# rcserial60b50ttl.net
KiCad netlist of a schematic drawn in EAGLE
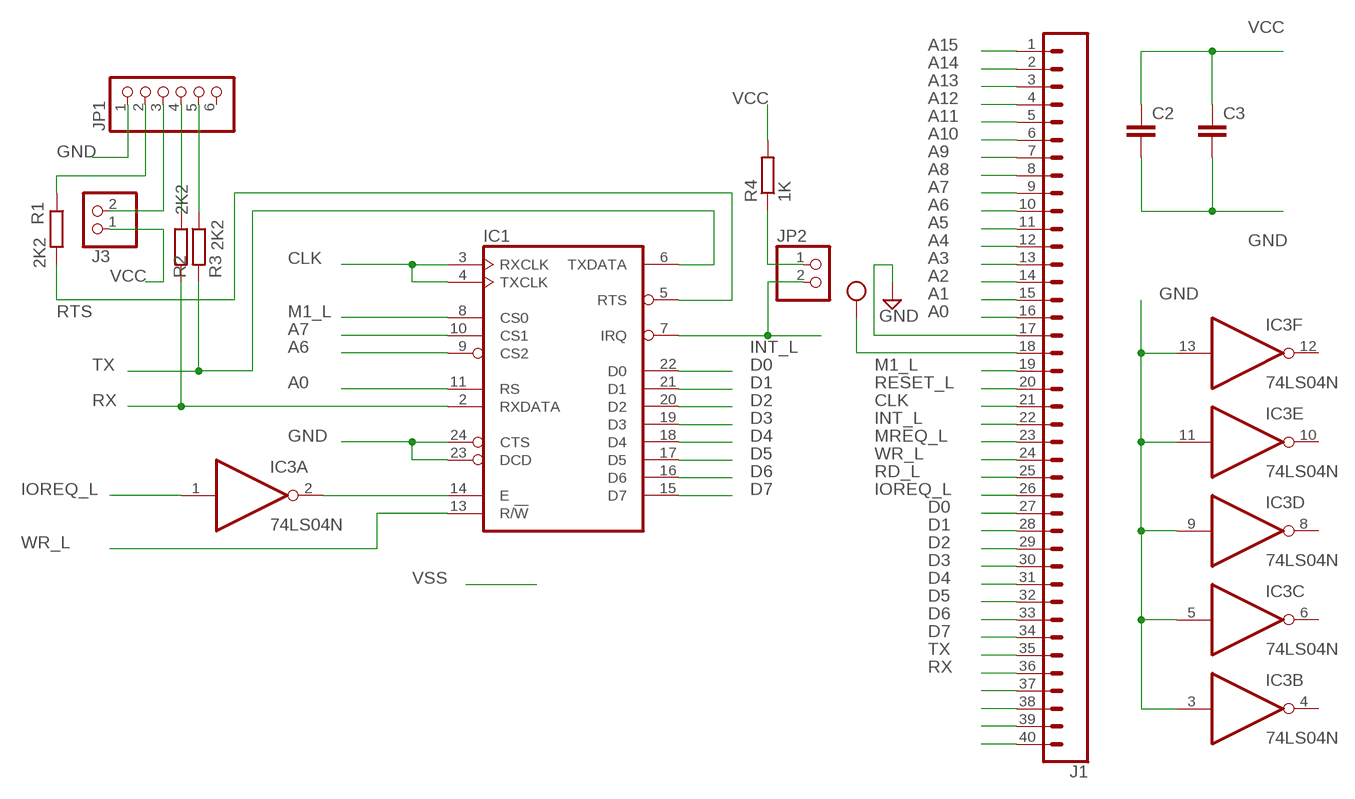
[diagram p0: schematic, sheet 1]

(export (version "E")
  (design (tool "Eeschema 10.0.6"))
  (components
    (comp (ref "C2")
      (value "C-EU050-025X075")
      (footprint "eagle-import:C050-025X075")
      (libsource (lib "eagle-import") (part "C-EU050-025X075"))
    )
    (comp (ref "C3")
      (value "C-EU050-025X075")
      (footprint "eagle-import:C050-025X075")
      (libsource (lib "eagle-import") (part "C-EU050-025X075"))
    )
    (comp (ref "IC1")
      (value "6850")
      (footprint "eagle-import:DIL24")
      (fields (field (name "MF") "NTE ELECTRONICS") (field (name "MPN") "NTE6850"))
      (libsource (lib "eagle-import") (part "6850"))
    )
    (comp (ref "IC3")
      (value "74LS04N")
      (footprint "eagle-import:DIL14")
      (libsource (lib "eagle-import") (part "7404NLS"))
    )
    (comp (ref "J1")
      (value "CONN_40OFFSET")
      (footprint "eagle-import:1X40_OFFSET")
      (libsource (lib "eagle-import") (part "CONN_40OFFSET"))
    )
    (comp (ref "J3")
      (value "PINHD-1X2")
      (footprint "eagle-import:1X02")
      (libsource (lib "eagle-import") (part "PINHD-1X2"))
    )
    (comp (ref "JP1")
      (value "PINHD-1X6")
      (footprint "eagle-import:1X06")
      (libsource (lib "eagle-import") (part "PINHD-1X6"))
    )
    (comp (ref "JP2")
      (value "PINHD-1X2")
      (footprint "eagle-import:1X02")
      (libsource (lib "eagle-import") (part "PINHD-1X2"))
    )
    (comp (ref "R1")
      (value "2K2")
      (footprint "eagle-import:0204_7")
      (libsource (lib "eagle-import") (part "R-EU_0204/7"))
    )
    (comp (ref "R2")
      (value "2K2")
      (footprint "eagle-import:0204_7")
      (libsource (lib "eagle-import") (part "R-EU_0204/7"))
    )
    (comp (ref "R3")
      (value "2K2")
      (footprint "eagle-import:0204_7")
      (libsource (lib "eagle-import") (part "R-EU_0204/7"))
    )
    (comp (ref "R4")
      (value "1K")
      (footprint "eagle-import:0204_7")
      (libsource (lib "eagle-import") (part "R-EU_0204/7"))
    )
  )
  (nets
    (net (code "1") (name "/A0") (class "Default")
      (node (ref "IC1") (pin "11") (pinfunction "RS_11") (pintype "input"))
      (node (ref "J1") (pin "16") (pinfunction "16_16") (pintype "passive"))
    )
    (net (code "2") (name "/A1") (class "Default")
      (node (ref "J1") (pin "15") (pinfunction "15_15") (pintype "passive"))
    )
    (net (code "3") (name "/A2") (class "Default")
      (node (ref "J1") (pin "14") (pinfunction "14_14") (pintype "passive"))
    )
    (net (code "4") (name "/A3") (class "Default")
      (node (ref "J1") (pin "13") (pinfunction "13_13") (pintype "passive"))
    )
    (net (code "5") (name "/A4") (class "Default")
      (node (ref "J1") (pin "12") (pinfunction "12_12") (pintype "passive"))
    )
    (net (code "6") (name "/A5") (class "Default")
      (node (ref "J1") (pin "11") (pinfunction "11_11") (pintype "passive"))
    )
    (net (code "7") (name "/A6") (class "Default")
      (node (ref "IC1") (pin "9") (pinfunction "CS2_9") (pintype "input"))
      (node (ref "J1") (pin "10") (pinfunction "10_10") (pintype "passive"))
    )
    (net (code "8") (name "/A7") (class "Default")
      (node (ref "IC1") (pin "10") (pinfunction "CS1_10") (pintype "input"))
      (node (ref "J1") (pin "9") (pinfunction "9_9") (pintype "passive"))
    )
    (net (code "9") (name "/A8") (class "Default")
      (node (ref "J1") (pin "8") (pinfunction "8_8") (pintype "passive"))
    )
    (net (code "10") (name "/A9") (class "Default")
      (node (ref "J1") (pin "7") (pinfunction "7_7") (pintype "passive"))
    )
    (net (code "11") (name "/A10") (class "Default")
      (node (ref "J1") (pin "6") (pinfunction "6_6") (pintype "passive"))
    )
    (net (code "12") (name "/A11") (class "Default")
      (node (ref "J1") (pin "5") (pinfunction "5_5") (pintype "passive"))
    )
    (net (code "13") (name "/A12") (class "Default")
      (node (ref "J1") (pin "4") (pinfunction "4_4") (pintype "passive"))
    )
    (net (code "14") (name "/A13") (class "Default")
      (node (ref "J1") (pin "3") (pinfunction "3_3") (pintype "passive"))
    )
    (net (code "15") (name "/A14") (class "Default")
      (node (ref "J1") (pin "2") (pinfunction "2_2") (pintype "passive"))
    )
    (net (code "16") (name "/A15") (class "Default")
      (node (ref "J1") (pin "1") (pinfunction "1_1") (pintype "passive"))
    )
    (net (code "17") (name "/CLK") (class "Default")
      (node (ref "IC1") (pin "3") (pinfunction "RXCLK_3") (pintype "input"))
      (node (ref "IC1") (pin "4") (pinfunction "TXCLK_4") (pintype "input"))
      (node (ref "J1") (pin "21") (pinfunction "21_21") (pintype "passive"))
    )
    (net (code "18") (name "/D0") (class "Default")
      (node (ref "IC1") (pin "22") (pinfunction "D0_22") (pintype "bidirectional"))
      (node (ref "J1") (pin "27") (pinfunction "27_27") (pintype "passive"))
    )
    (net (code "19") (name "/D1") (class "Default")
      (node (ref "IC1") (pin "21") (pinfunction "D1_21") (pintype "bidirectional"))
      (node (ref "J1") (pin "28") (pinfunction "28_28") (pintype "passive"))
    )
    (net (code "20") (name "/D2") (class "Default")
      (node (ref "IC1") (pin "20") (pinfunction "D2_20") (pintype "bidirectional"))
      (node (ref "J1") (pin "29") (pinfunction "29_29") (pintype "passive"))
    )
    (net (code "21") (name "/D3") (class "Default")
      (node (ref "IC1") (pin "19") (pinfunction "D3_19") (pintype "bidirectional"))
      (node (ref "J1") (pin "30") (pinfunction "30_30") (pintype "passive"))
    )
    (net (code "22") (name "/D4") (class "Default")
      (node (ref "IC1") (pin "18") (pinfunction "D4_18") (pintype "bidirectional"))
      (node (ref "J1") (pin "31") (pinfunction "31_31") (pintype "passive"))
    )
    (net (code "23") (name "/D5") (class "Default")
      (node (ref "IC1") (pin "17") (pinfunction "D5_17") (pintype "bidirectional"))
      (node (ref "J1") (pin "32") (pinfunction "32_32") (pintype "passive"))
    )
    (net (code "24") (name "/D6") (class "Default")
      (node (ref "IC1") (pin "16") (pinfunction "D6_16") (pintype "bidirectional"))
      (node (ref "J1") (pin "33") (pinfunction "33_33") (pintype "passive"))
    )
    (net (code "25") (name "/D7") (class "Default")
      (node (ref "IC1") (pin "15") (pinfunction "D7_15") (pintype "bidirectional"))
      (node (ref "J1") (pin "34") (pinfunction "34_34") (pintype "passive"))
    )
    (net (code "26") (name "/INT_L") (class "Default")
      (node (ref "IC1") (pin "7") (pinfunction "IRQ_7") (pintype "output"))
      (node (ref "J1") (pin "22") (pinfunction "22_22") (pintype "passive"))
      (node (ref "JP2") (pin "2") (pinfunction "2_2") (pintype "passive"))
    )
    (net (code "27") (name "/IOREQ_L") (class "Default")
      (node (ref "IC3") (pin "1") (pinfunction "I_1") (pintype "input"))
      (node (ref "J1") (pin "26") (pinfunction "26_26") (pintype "passive"))
    )
    (net (code "28") (name "/M1_L") (class "Default")
      (node (ref "IC1") (pin "8") (pinfunction "CS0_8") (pintype "input"))
      (node (ref "J1") (pin "19") (pinfunction "19_19") (pintype "passive"))
    )
    (net (code "29") (name "/MREQ_L") (class "Default")
      (node (ref "J1") (pin "23") (pinfunction "23_23") (pintype "passive"))
    )
    (net (code "30") (name "/RD_L") (class "Default")
      (node (ref "J1") (pin "25") (pinfunction "25_25") (pintype "passive"))
    )
    (net (code "31") (name "/RESET_L") (class "Default")
      (node (ref "J1") (pin "20") (pinfunction "20_20") (pintype "passive"))
    )
    (net (code "32") (name "/RTS") (class "Default")
      (node (ref "IC1") (pin "5") (pinfunction "RTS_5") (pintype "output"))
      (node (ref "R1") (pin "2") (pinfunction "2_2") (pintype "passive"))
    )
    (net (code "33") (name "/RX") (class "Default")
      (node (ref "IC1") (pin "2") (pinfunction "RXDATA_2") (pintype "input"))
      (node (ref "J1") (pin "36") (pinfunction "36_36") (pintype "passive"))
      (node (ref "R2") (pin "2") (pinfunction "2_2") (pintype "passive"))
    )
    (net (code "34") (name "/TX") (class "Default")
      (node (ref "IC1") (pin "6") (pinfunction "TXDATA_6") (pintype "output"))
      (node (ref "J1") (pin "35") (pinfunction "35_35") (pintype "passive"))
      (node (ref "R3") (pin "2") (pinfunction "2_2") (pintype "passive"))
    )
    (net (code "36") (name "/WR_L") (class "Default")
      (node (ref "IC1") (pin "13") (pinfunction "R/~{W}_13") (pintype "input"))
      (node (ref "J1") (pin "24") (pinfunction "24_24") (pintype "passive"))
    )
    (net (code "37") (name "GND") (class "Default")
      (node (ref "C2") (pin "2") (pinfunction "2_2") (pintype "passive"))
      (node (ref "C3") (pin "2") (pinfunction "2_2") (pintype "passive"))
      (node (ref "IC1") (pin "23") (pinfunction "DCD_23") (pintype "input"))
      (node (ref "IC1") (pin "24") (pinfunction "CTS_24") (pintype "input"))
      (node (ref "IC3") (pin "11") (pinfunction "I_11") (pintype "input"))
      (node (ref "IC3") (pin "13") (pinfunction "I_13") (pintype "input"))
      (node (ref "IC3") (pin "3") (pinfunction "I_3") (pintype "input"))
      (node (ref "IC3") (pin "5") (pinfunction "I_5") (pintype "input"))
      (node (ref "IC3") (pin "9") (pinfunction "I_9") (pintype "input"))
      (node (ref "J1") (pin "17") (pinfunction "17_17") (pintype "passive"))
      (node (ref "JP1") (pin "1") (pinfunction "1_1") (pintype "passive"))
    )
    (net (code "38") (name "Net-(IC1A-E)") (class "Default")
      (node (ref "IC1") (pin "14") (pinfunction "E_14") (pintype "input"))
      (node (ref "IC3") (pin "2") (pinfunction "O_2") (pintype "output"))
    )
    (net (code "39") (name "Net-(J3-Pad2)") (class "Default")
      (node (ref "J3") (pin "2") (pinfunction "2_2") (pintype "passive"))
      (node (ref "JP1") (pin "3") (pinfunction "3_3") (pintype "passive"))
    )
    (net (code "40") (name "Net-(JP1-Pad2)") (class "Default")
      (node (ref "JP1") (pin "2") (pinfunction "2_2") (pintype "passive"))
      (node (ref "R1") (pin "1") (pinfunction "1_1") (pintype "passive"))
    )
    (net (code "41") (name "Net-(JP1-Pad4)") (class "Default")
      (node (ref "JP1") (pin "4") (pinfunction "4_4") (pintype "passive"))
      (node (ref "R2") (pin "1") (pinfunction "1_1") (pintype "passive"))
    )
    (net (code "42") (name "Net-(JP1-Pad5)") (class "Default")
      (node (ref "JP1") (pin "5") (pinfunction "5_5") (pintype "passive"))
      (node (ref "R3") (pin "1") (pinfunction "1_1") (pintype "passive"))
    )
    (net (code "43") (name "Net-(JP2-Pad1)") (class "Default")
      (node (ref "JP2") (pin "1") (pinfunction "1_1") (pintype "passive"))
      (node (ref "R4") (pin "1") (pinfunction "1_1") (pintype "passive"))
    )
    (net (code "44") (name "VCC") (class "Default")
      (node (ref "C2") (pin "1") (pinfunction "1_1") (pintype "passive"))
      (node (ref "C3") (pin "1") (pinfunction "1_1") (pintype "passive"))
      (node (ref "J1") (pin "18") (pinfunction "18_18") (pintype "passive"))
      (node (ref "J3") (pin "1") (pinfunction "1_1") (pintype "passive"))
      (node (ref "R4") (pin "2") (pinfunction "2_2") (pintype "passive"))
    )
    (net (code "45") (name "unconnected-(IC3B-O-Pad4)") (class "Default")
      (node (ref "IC3") (pin "4") (pinfunction "O_4") (pintype "output"))
    )
    (net (code "46") (name "unconnected-(IC3C-O-Pad6)") (class "Default")
      (node (ref "IC3") (pin "6") (pinfunction "O_6") (pintype "output"))
    )
    (net (code "47") (name "unconnected-(IC3D-O-Pad8)") (class "Default")
      (node (ref "IC3") (pin "8") (pinfunction "O_8") (pintype "output"))
    )
    (net (code "48") (name "unconnected-(IC3E-O-Pad10)") (class "Default")
      (node (ref "IC3") (pin "10") (pinfunction "O_10") (pintype "output"))
    )
    (net (code "49") (name "unconnected-(IC3F-O-Pad12)") (class "Default")
      (node (ref "IC3") (pin "12") (pinfunction "O_12") (pintype "output"))
    )
    (net (code "50") (name "unconnected-(J1-Pad37)") (class "Default")
      (node (ref "J1") (pin "37") (pinfunction "37_37") (pintype "passive"))
    )
    (net (code "51") (name "unconnected-(J1-Pad38)") (class "Default")
      (node (ref "J1") (pin "38") (pinfunction "38_38") (pintype "passive"))
    )
    (net (code "52") (name "unconnected-(J1-Pad39)") (class "Default")
      (node (ref "J1") (pin "39") (pinfunction "39_39") (pintype "passive"))
    )
    (net (code "53") (name "unconnected-(J1-Pad40)") (class "Default")
      (node (ref "J1") (pin "40") (pinfunction "40_40") (pintype "passive"))
    )
    (net (code "54") (name "unconnected-(JP1-Pad6)") (class "Default")
      (node (ref "JP1") (pin "6") (pinfunction "6_6") (pintype "passive"))
    )
  )
)
